# NAU7802.net
KiCad netlist of a schematic drawn in EAGLE
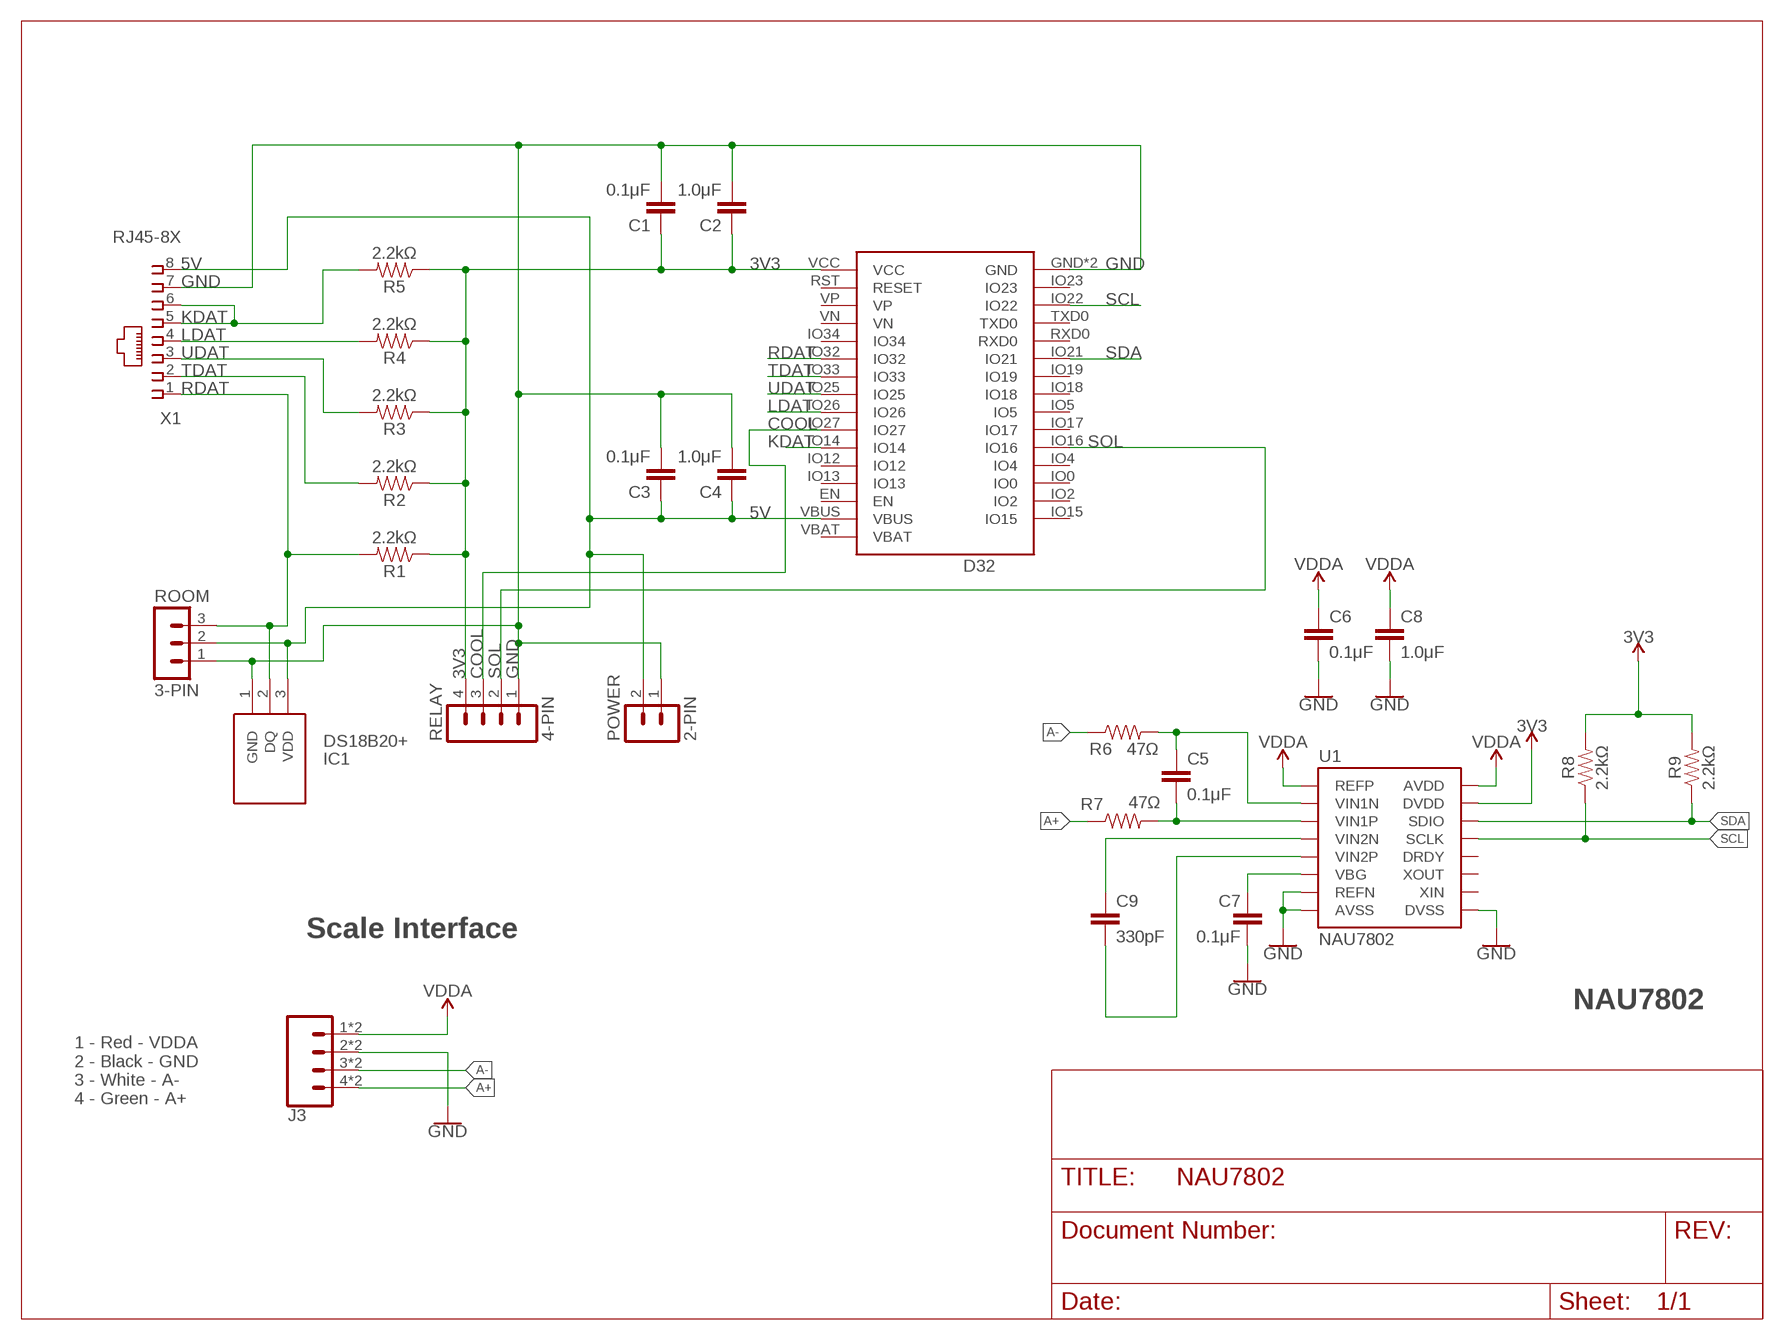
[diagram p0: schematic, sheet 1]

(export (version "E")
  (design (tool "Eeschema 10.0.6"))
  (components
    (comp (ref "C1")
      (value "0.1μF")
      (footprint "eagle-import:CAP_PTH-2.54")
      (libsource (lib "eagle-import") (part "CAP_CERAMIC_2.54"))
    )
    (comp (ref "C2")
      (value "1.0μF")
      (footprint "eagle-import:CAP_PTH-2.54")
      (libsource (lib "eagle-import") (part "CAP_CERAMIC_2.54"))
    )
    (comp (ref "C3")
      (value "0.1μF")
      (footprint "eagle-import:CAP_PTH-2.54")
      (libsource (lib "eagle-import") (part "CAP_CERAMIC_2.54"))
    )
    (comp (ref "C4")
      (value "1.0μF")
      (footprint "eagle-import:CAP_PTH-2.54")
      (libsource (lib "eagle-import") (part "CAP_CERAMIC_2.54"))
    )
    (comp (ref "C5")
      (value "0.1μF")
      (footprint "eagle-import:C025-024X044")
      (libsource (lib "eagle-import") (part "C-EU025-024X044"))
    )
    (comp (ref "C6")
      (value "0.1μF")
      (footprint "eagle-import:C025-024X044")
      (libsource (lib "eagle-import") (part "C-EU025-024X044"))
    )
    (comp (ref "C7")
      (value "0.1μF")
      (footprint "eagle-import:C025-024X044")
      (libsource (lib "eagle-import") (part "C-EU025-024X044"))
    )
    (comp (ref "C8")
      (value "1.0μF")
      (footprint "eagle-import:C025-024X044")
      (libsource (lib "eagle-import") (part "C-EU025-024X044"))
    )
    (comp (ref "C9")
      (value "330pF")
      (footprint "eagle-import:C025-024X044")
      (libsource (lib "eagle-import") (part "C-EU025-024X044"))
    )
    (comp (ref "D32")
      (value "Lolin D32")
      (footprint "eagle-import:D32_NO_BATT")
      (libsource (lib "eagle-import") (part "WEMOS-D32D32_NO_BATT"))
    )
    (comp (ref "IC1")
      (value "DS18B20+")
      (footprint "eagle-import:TO-92")
      (fields (field (name "MOUSER_PART_NUMBER") "700-DS18B20+"))
      (libsource (lib "eagle-import") (part "DS18B20+"))
    )
    (comp (ref "J3")
      (value "Spring Terminal")
      (footprint "eagle-import:1X04_SPRING_TERMINAL")
      (libsource (lib "eagle-import") (part "CONN_04SPRING"))
    )
    (comp (ref "POWER")
      (value "2-PIN")
      (footprint "eagle-import:HDR-2_VERT")
      (libsource (lib "eagle-import") (part "HDR-2"))
    )
    (comp (ref "R1")
      (value "2.2kΩ")
      (footprint "eagle-import:AXIAL-0.3")
      (libsource (lib "eagle-import") (part "RESISTORAXIAL-0.3"))
    )
    (comp (ref "R2")
      (value "2.2kΩ")
      (footprint "eagle-import:AXIAL-0.3")
      (libsource (lib "eagle-import") (part "RESISTORAXIAL-0.3"))
    )
    (comp (ref "R3")
      (value "2.2kΩ")
      (footprint "eagle-import:AXIAL-0.3")
      (libsource (lib "eagle-import") (part "RESISTORAXIAL-0.3"))
    )
    (comp (ref "R4")
      (value "2.2kΩ")
      (footprint "eagle-import:AXIAL-0.3")
      (libsource (lib "eagle-import") (part "RESISTORAXIAL-0.3"))
    )
    (comp (ref "R5")
      (value "2.2kΩ")
      (footprint "eagle-import:AXIAL-0.3")
      (libsource (lib "eagle-import") (part "RESISTORAXIAL-0.3"))
    )
    (comp (ref "R6")
      (value "47Ω")
      (footprint "eagle-import:AXIAL-0.3")
      (libsource (lib "eagle-import") (part "1KOHM-HORIZ-1/4W-5%"))
    )
    (comp (ref "R7")
      (value "47Ω")
      (footprint "eagle-import:AXIAL-0.3")
      (libsource (lib "eagle-import") (part "1KOHM-HORIZ-1/4W-5%"))
    )
    (comp (ref "R8")
      (value "2.2kΩ")
      (footprint "eagle-import:AXIAL-0.3")
      (libsource (lib "eagle-import") (part "1KOHM-HORIZ-1/4W-5%"))
    )
    (comp (ref "R9")
      (value "2.2kΩ")
      (footprint "eagle-import:AXIAL-0.3")
      (libsource (lib "eagle-import") (part "1KOHM-HORIZ-1/4W-5%"))
    )
    (comp (ref "RELAY")
      (value "4-PIN")
      (footprint "eagle-import:MA04-1")
      (libsource (lib "eagle-import") (part "MA04-1"))
    )
    (comp (ref "ROOM")
      (value "3-PIN")
      (footprint "eagle-import:HDR-3_VERT")
      (libsource (lib "eagle-import") (part "HDR-3"))
    )
    (comp (ref "U1")
      (value "NAU7802")
      (footprint "eagle-import:DIP16")
      (libsource (lib "eagle-import") (part "NAU7802DIP16"))
    )
    (comp (ref "X1")
      (value "RJ45-8X")
      (footprint "eagle-import:RJ45-NO-SHIELD")
      (libsource (lib "eagle-import") (part "RJ45-8X"))
    )
  )
  (nets
    (net (code "1") (name "/5V") (class "Default")
      (node (ref "C3") (pin "1") (pinfunction "1_1") (pintype "passive"))
      (node (ref "C4") (pin "1") (pinfunction "1_1") (pintype "passive"))
      (node (ref "D32") (pin "VBUS") (pinfunction "VBUS_VBUS") (pintype "bidirectional"))
      (node (ref "IC1") (pin "3") (pinfunction "VDD_3") (pintype "power_in"))
      (node (ref "POWER") (pin "2") (pinfunction "2_2") (pintype "passive"))
      (node (ref "ROOM") (pin "2") (pinfunction "2_2") (pintype "passive"))
      (node (ref "X1") (pin "8") (pinfunction "8_8") (pintype "passive"))
    )
    (net (code "2") (name "/COOL") (class "Default")
      (node (ref "D32") (pin "IO27") (pinfunction "IO27_IO27") (pintype "bidirectional"))
      (node (ref "RELAY") (pin "3") (pinfunction "3_3") (pintype "passive"))
    )
    (net (code "3") (name "/KDAT") (class "Default")
      (node (ref "D32") (pin "IO14") (pinfunction "IO14_IO14") (pintype "bidirectional"))
      (node (ref "R5") (pin "P$2") (pinfunction "2_P$2") (pintype "passive"))
      (node (ref "X1") (pin "5") (pinfunction "5_5") (pintype "passive"))
      (node (ref "X1") (pin "6") (pinfunction "6_6") (pintype "passive"))
    )
    (net (code "4") (name "/LDAT") (class "Default")
      (node (ref "D32") (pin "IO26") (pinfunction "IO26_IO26") (pintype "bidirectional"))
      (node (ref "R4") (pin "P$2") (pinfunction "2_P$2") (pintype "passive"))
      (node (ref "X1") (pin "4") (pinfunction "4_4") (pintype "passive"))
    )
    (net (code "5") (name "/RDAT") (class "Default")
      (node (ref "D32") (pin "IO32") (pinfunction "IO32_IO32") (pintype "bidirectional"))
      (node (ref "IC1") (pin "2") (pinfunction "DQ_2") (pintype "bidirectional"))
      (node (ref "R1") (pin "P$2") (pinfunction "2_P$2") (pintype "passive"))
      (node (ref "ROOM") (pin "3") (pinfunction "3_3") (pintype "passive"))
      (node (ref "X1") (pin "1") (pinfunction "1_1") (pintype "passive"))
    )
    (net (code "6") (name "/SOL") (class "Default")
      (node (ref "D32") (pin "IO16") (pinfunction "IO16_IO16") (pintype "bidirectional"))
      (node (ref "RELAY") (pin "2") (pinfunction "2_2") (pintype "passive"))
    )
    (net (code "7") (name "/TDAT") (class "Default")
      (node (ref "D32") (pin "IO33") (pinfunction "IO33_IO33") (pintype "bidirectional"))
      (node (ref "R2") (pin "P$2") (pinfunction "2_P$2") (pintype "passive"))
      (node (ref "X1") (pin "2") (pinfunction "2_2") (pintype "passive"))
    )
    (net (code "8") (name "/UDAT") (class "Default")
      (node (ref "D32") (pin "IO25") (pinfunction "IO25_IO25") (pintype "bidirectional"))
      (node (ref "R3") (pin "P$2") (pinfunction "2_P$2") (pintype "passive"))
      (node (ref "X1") (pin "3") (pinfunction "3_3") (pintype "passive"))
    )
    (net (code "9") (name "3.3V") (class "Default")
      (node (ref "C1") (pin "1") (pinfunction "1_1") (pintype "passive"))
      (node (ref "C2") (pin "1") (pinfunction "1_1") (pintype "passive"))
      (node (ref "D32") (pin "VCC") (pinfunction "VCC_VCC") (pintype "power_in"))
      (node (ref "R1") (pin "P$1") (pinfunction "1_P$1") (pintype "passive"))
      (node (ref "R2") (pin "P$1") (pinfunction "1_P$1") (pintype "passive"))
      (node (ref "R3") (pin "P$1") (pinfunction "1_P$1") (pintype "passive"))
      (node (ref "R4") (pin "P$1") (pinfunction "1_P$1") (pintype "passive"))
      (node (ref "R5") (pin "P$1") (pinfunction "1_P$1") (pintype "passive"))
      (node (ref "R8") (pin "P$2") (pinfunction "2_P$2") (pintype "passive"))
      (node (ref "R9") (pin "P$2") (pinfunction "2_P$2") (pintype "passive"))
      (node (ref "RELAY") (pin "4") (pinfunction "4_4") (pintype "passive"))
      (node (ref "U1") (pin "15") (pinfunction "DVDD_15") (pintype "bidirectional"))
    )
    (net (code "10") (name "A+") (class "Default")
      (node (ref "J3") (pin "4") (pinfunction "4_4") (pintype "passive"))
      (node (ref "J3") (pin "8") (pinfunction "4_8") (pintype "passive"))
      (node (ref "R7") (pin "P$1") (pinfunction "1_P$1") (pintype "passive"))
    )
    (net (code "11") (name "A-") (class "Default")
      (node (ref "J3") (pin "3") (pinfunction "3_3") (pintype "passive"))
      (node (ref "J3") (pin "7") (pinfunction "3_7") (pintype "passive"))
      (node (ref "R6") (pin "P$1") (pinfunction "1_P$1") (pintype "passive"))
    )
    (net (code "12") (name "GND") (class "Default")
      (node (ref "C1") (pin "2") (pinfunction "2_2") (pintype "passive"))
      (node (ref "C2") (pin "2") (pinfunction "2_2") (pintype "passive"))
      (node (ref "C3") (pin "2") (pinfunction "2_2") (pintype "passive"))
      (node (ref "C4") (pin "2") (pinfunction "2_2") (pintype "passive"))
      (node (ref "C6") (pin "2") (pinfunction "2_2") (pintype "passive"))
      (node (ref "C7") (pin "2") (pinfunction "2_2") (pintype "passive"))
      (node (ref "C8") (pin "2") (pinfunction "2_2") (pintype "passive"))
      (node (ref "D32") (pin "GND") (pinfunction "GND_GND") (pintype "power_in"))
      (node (ref "D32") (pin "GND2") (pinfunction "GND_GND2") (pintype "power_in"))
      (node (ref "IC1") (pin "1") (pinfunction "GND_1") (pintype "power_in"))
      (node (ref "J3") (pin "2") (pinfunction "2_2") (pintype "passive"))
      (node (ref "J3") (pin "6") (pinfunction "2_6") (pintype "passive"))
      (node (ref "POWER") (pin "1") (pinfunction "1_1") (pintype "passive"))
      (node (ref "RELAY") (pin "1") (pinfunction "1_1") (pintype "passive"))
      (node (ref "ROOM") (pin "1") (pinfunction "1_1") (pintype "passive"))
      (node (ref "U1") (pin "7") (pinfunction "REFN_7") (pintype "bidirectional"))
      (node (ref "U1") (pin "8") (pinfunction "AVSS_8") (pintype "bidirectional"))
      (node (ref "U1") (pin "9") (pinfunction "DVSS_9") (pintype "bidirectional"))
      (node (ref "X1") (pin "7") (pinfunction "7_7") (pintype "passive"))
    )
    (net (code "13") (name "Net-(R6-2)") (class "Default")
      (node (ref "C5") (pin "1") (pinfunction "1_1") (pintype "passive"))
      (node (ref "R6") (pin "P$2") (pinfunction "2_P$2") (pintype "passive"))
      (node (ref "U1") (pin "2") (pinfunction "VIN1N_2") (pintype "bidirectional"))
    )
    (net (code "14") (name "Net-(R7-2)") (class "Default")
      (node (ref "C5") (pin "2") (pinfunction "2_2") (pintype "passive"))
      (node (ref "R7") (pin "P$2") (pinfunction "2_P$2") (pintype "passive"))
      (node (ref "U1") (pin "3") (pinfunction "VIN1P_3") (pintype "bidirectional"))
    )
    (net (code "15") (name "Net-(U1-VBG)") (class "Default")
      (node (ref "C7") (pin "1") (pinfunction "1_1") (pintype "passive"))
      (node (ref "U1") (pin "6") (pinfunction "VBG_6") (pintype "bidirectional"))
    )
    (net (code "16") (name "Net-(U1-VIN2N)") (class "Default")
      (node (ref "C9") (pin "1") (pinfunction "1_1") (pintype "passive"))
      (node (ref "U1") (pin "4") (pinfunction "VIN2N_4") (pintype "bidirectional"))
    )
    (net (code "17") (name "Net-(U1-VIN2P)") (class "Default")
      (node (ref "C9") (pin "2") (pinfunction "2_2") (pintype "passive"))
      (node (ref "U1") (pin "5") (pinfunction "VIN2P_5") (pintype "bidirectional"))
    )
    (net (code "18") (name "SCL") (class "Default")
      (node (ref "D32") (pin "IO22") (pinfunction "IO22_IO22") (pintype "bidirectional"))
      (node (ref "R8") (pin "P$1") (pinfunction "1_P$1") (pintype "passive"))
      (node (ref "U1") (pin "13") (pinfunction "SCLK_13") (pintype "bidirectional"))
    )
    (net (code "19") (name "SDA") (class "Default")
      (node (ref "D32") (pin "IO21") (pinfunction "IO21_IO21") (pintype "bidirectional"))
      (node (ref "R9") (pin "P$1") (pinfunction "1_P$1") (pintype "passive"))
      (node (ref "U1") (pin "14") (pinfunction "SDIO_14") (pintype "bidirectional"))
    )
    (net (code "20") (name "VDDA") (class "Default")
      (node (ref "C6") (pin "1") (pinfunction "1_1") (pintype "passive"))
      (node (ref "C8") (pin "1") (pinfunction "1_1") (pintype "passive"))
      (node (ref "J3") (pin "1") (pinfunction "1_1") (pintype "passive"))
      (node (ref "J3") (pin "5") (pinfunction "1_5") (pintype "passive"))
      (node (ref "U1") (pin "1") (pinfunction "REFP_1") (pintype "bidirectional"))
      (node (ref "U1") (pin "16") (pinfunction "AVDD_16") (pintype "bidirectional"))
    )
    (net (code "21") (name "unconnected-(D32-PadEN)") (class "Default")
      (node (ref "D32") (pin "EN") (pinfunction "EN_EN") (pintype "bidirectional"))
    )
    (net (code "22") (name "unconnected-(D32-PadIO0)") (class "Default")
      (node (ref "D32") (pin "IO0") (pinfunction "IO0_IO0") (pintype "bidirectional"))
    )
    (net (code "23") (name "unconnected-(D32-PadIO2)") (class "Default")
      (node (ref "D32") (pin "IO2") (pinfunction "IO2_IO2") (pintype "bidirectional"))
    )
    (net (code "24") (name "unconnected-(D32-PadIO4)") (class "Default")
      (node (ref "D32") (pin "IO4") (pinfunction "IO4_IO4") (pintype "bidirectional"))
    )
    (net (code "25") (name "unconnected-(D32-PadIO5)") (class "Default")
      (node (ref "D32") (pin "IO5") (pinfunction "IO5_IO5") (pintype "bidirectional"))
    )
    (net (code "26") (name "unconnected-(D32-PadIO12)") (class "Default")
      (node (ref "D32") (pin "IO12") (pinfunction "IO12_IO12") (pintype "bidirectional"))
    )
    (net (code "27") (name "unconnected-(D32-PadIO13)") (class "Default")
      (node (ref "D32") (pin "IO13") (pinfunction "IO13_IO13") (pintype "bidirectional"))
    )
    (net (code "28") (name "unconnected-(D32-PadIO15)") (class "Default")
      (node (ref "D32") (pin "IO15") (pinfunction "IO15_IO15") (pintype "bidirectional"))
    )
    (net (code "29") (name "unconnected-(D32-PadIO17)") (class "Default")
      (node (ref "D32") (pin "IO17") (pinfunction "IO17_IO17") (pintype "bidirectional"))
    )
    (net (code "30") (name "unconnected-(D32-PadIO18)") (class "Default")
      (node (ref "D32") (pin "IO18") (pinfunction "IO18_IO18") (pintype "bidirectional"))
    )
    (net (code "31") (name "unconnected-(D32-PadIO19)") (class "Default")
      (node (ref "D32") (pin "IO19") (pinfunction "IO19_IO19") (pintype "bidirectional"))
    )
    (net (code "32") (name "unconnected-(D32-PadIO23)") (class "Default")
      (node (ref "D32") (pin "IO23") (pinfunction "IO23_IO23") (pintype "bidirectional"))
    )
    (net (code "33") (name "unconnected-(D32-PadIO34)") (class "Default")
      (node (ref "D32") (pin "IO34") (pinfunction "IO34_IO34") (pintype "bidirectional"))
    )
    (net (code "34") (name "unconnected-(D32-PadRXD0)") (class "Default")
      (node (ref "D32") (pin "RXD0") (pinfunction "RXD0_RXD0") (pintype "input"))
    )
    (net (code "35") (name "unconnected-(D32-PadTXD0)") (class "Default")
      (node (ref "D32") (pin "TXD0") (pinfunction "TXD0_TXD0") (pintype "output"))
    )
    (net (code "36") (name "unconnected-(D32-PadVBAT)") (class "Default")
      (node (ref "D32") (pin "VBAT") (pinfunction "VBAT_VBAT") (pintype "bidirectional"))
    )
    (net (code "37") (name "unconnected-(D32-PadVN)") (class "Default")
      (node (ref "D32") (pin "VN") (pinfunction "VN_VN") (pintype "bidirectional"))
    )
    (net (code "38") (name "unconnected-(D32-PadVP)") (class "Default")
      (node (ref "D32") (pin "VP") (pinfunction "VP_VP") (pintype "bidirectional"))
    )
    (net (code "39") (name "unconnected-(D32-RESET-PadRST)") (class "Default")
      (node (ref "D32") (pin "RST") (pinfunction "RESET_RST") (pintype "bidirectional"))
    )
    (net (code "40") (name "unconnected-(U1-DRDY-Pad12)") (class "Default")
      (node (ref "U1") (pin "12") (pinfunction "DRDY_12") (pintype "bidirectional"))
    )
    (net (code "41") (name "unconnected-(U1-XIN-Pad10)") (class "Default")
      (node (ref "U1") (pin "10") (pinfunction "XIN_10") (pintype "bidirectional"))
    )
    (net (code "42") (name "unconnected-(U1-XOUT-Pad11)") (class "Default")
      (node (ref "U1") (pin "11") (pinfunction "XOUT_11") (pintype "bidirectional"))
    )
  )
)
